# MSP430FR2433_SMD_0603.net
KiCad netlist of a schematic drawn in EAGLE
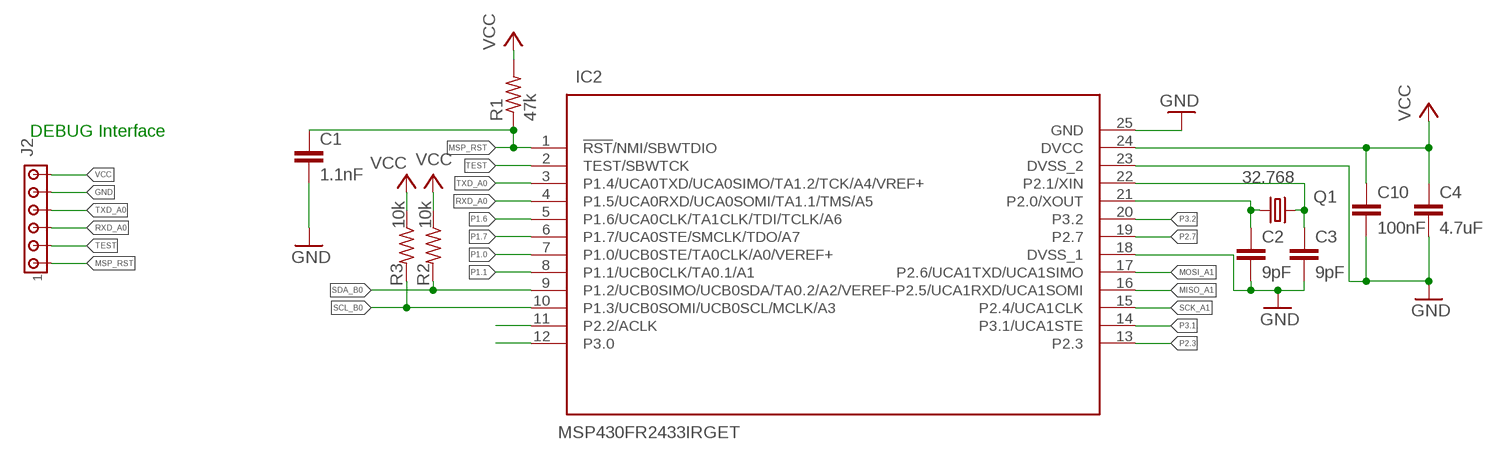
[diagram p0: schematic, sheet 1]

(export (version "E")
  (design (tool "Eeschema 10.0.6"))
  (components
    (comp (ref "C1")
      (value "1.1nF")
      (footprint "eagle-import:C0402")
      (libsource (lib "eagle-import") (part "C-EUC0402"))
    )
    (comp (ref "C2")
      (value "9pF")
      (footprint "eagle-import:C0402")
      (libsource (lib "eagle-import") (part "C-EUC0402"))
    )
    (comp (ref "C3")
      (value "9pF")
      (footprint "eagle-import:C0402")
      (libsource (lib "eagle-import") (part "C-EUC0402"))
    )
    (comp (ref "C4")
      (value "4.7uF")
      (footprint "eagle-import:C0402")
      (libsource (lib "eagle-import") (part "C-EUC0402"))
    )
    (comp (ref "C10")
      (value "100nF")
      (footprint "eagle-import:C0402")
      (libsource (lib "eagle-import") (part "C-EUC0402"))
    )
    (comp (ref "IC2")
      (value "MSP430FR2433IRGET")
      (footprint "eagle-import:QFN50P400X400X100-25N")
      (fields (field (name "MOUSER_PART_NUMBER") "595-SP430FR2433IRGET"))
      (libsource (lib "eagle-import") (part "MSP430FR2433IRGET"))
    )
    (comp (ref "J2")
      (value "MTA06-100")
      (footprint "eagle-import:10X06MTA")
      (libsource (lib "eagle-import") (part "MTA06-100"))
    )
    (comp (ref "Q1")
      (value "32.768")
      (footprint "eagle-import:TC26H")
      (libsource (lib "eagle-import") (part "CRYTALTC26H"))
    )
    (comp (ref "R1")
      (value "47k")
      (footprint "eagle-import:R0402")
      (libsource (lib "eagle-import") (part "R-US_R0402"))
    )
    (comp (ref "R2")
      (value "10k")
      (footprint "eagle-import:R0402")
      (libsource (lib "eagle-import") (part "R-US_R0402"))
    )
    (comp (ref "R3")
      (value "10k")
      (footprint "eagle-import:R0402")
      (libsource (lib "eagle-import") (part "R-US_R0402"))
    )
  )
  (nets
    (net (code "1") (name "GND") (class "Default")
      (node (ref "C1") (pin "2") (pinfunction "2_2") (pintype "passive"))
      (node (ref "C10") (pin "2") (pinfunction "2_2") (pintype "passive"))
      (node (ref "C2") (pin "2") (pinfunction "2_2") (pintype "passive"))
      (node (ref "C3") (pin "2") (pinfunction "2_2") (pintype "passive"))
      (node (ref "C4") (pin "2") (pinfunction "2_2") (pintype "passive"))
      (node (ref "IC2") (pin "18") (pinfunction "DVSS_1_18") (pintype "bidirectional"))
      (node (ref "IC2") (pin "23") (pinfunction "DVSS_2_23") (pintype "bidirectional"))
      (node (ref "IC2") (pin "25") (pinfunction "GND_25") (pintype "bidirectional"))
      (node (ref "J2") (pin "5") (pinfunction "5_5") (pintype "passive"))
    )
    (net (code "2") (name "MISO_A1") (class "Default")
      (node (ref "IC2") (pin "16") (pinfunction "P2.5/UCA1RXD/UCA1SOMI_16") (pintype "bidirectional"))
    )
    (net (code "3") (name "MOSI_A1") (class "Default")
      (node (ref "IC2") (pin "17") (pinfunction "P2.6/UCA1TXD/UCA1SIMO_17") (pintype "bidirectional"))
    )
    (net (code "4") (name "MSP_RST") (class "Default")
      (node (ref "C1") (pin "1") (pinfunction "1_1") (pintype "passive"))
      (node (ref "IC2") (pin "1") (pinfunction "~{RST}/NMI/SBWTDIO_1") (pintype "bidirectional"))
      (node (ref "J2") (pin "1") (pinfunction "1_1") (pintype "passive"))
      (node (ref "R1") (pin "1") (pinfunction "1_1") (pintype "passive"))
    )
    (net (code "5") (name "Net-(IC2-P2.0{slash}XOUT)") (class "Default")
      (node (ref "C2") (pin "1") (pinfunction "1_1") (pintype "passive"))
      (node (ref "IC2") (pin "21") (pinfunction "P2.0/XOUT_21") (pintype "bidirectional"))
      (node (ref "Q1") (pin "1") (pinfunction "1_1") (pintype "passive"))
    )
    (net (code "6") (name "Net-(IC2-P2.1{slash}XIN)") (class "Default")
      (node (ref "C3") (pin "1") (pinfunction "1_1") (pintype "passive"))
      (node (ref "IC2") (pin "22") (pinfunction "P2.1/XIN_22") (pintype "bidirectional"))
      (node (ref "Q1") (pin "2") (pinfunction "2_2") (pintype "passive"))
    )
    (net (code "7") (name "P1.0") (class "Default")
      (node (ref "IC2") (pin "7") (pinfunction "P1.0/UCB0STE/TA0CLK/A0/VEREF+_7") (pintype "bidirectional"))
    )
    (net (code "8") (name "P1.1") (class "Default")
      (node (ref "IC2") (pin "8") (pinfunction "P1.1/UCB0CLK/TA0.1/A1_8") (pintype "bidirectional"))
    )
    (net (code "9") (name "P1.6") (class "Default")
      (node (ref "IC2") (pin "5") (pinfunction "P1.6/UCA0CLK/TA1CLK/TDI/TCLK/A6_5") (pintype "bidirectional"))
    )
    (net (code "10") (name "P1.7") (class "Default")
      (node (ref "IC2") (pin "6") (pinfunction "P1.7/UCA0STE/SMCLK/TDO/A7_6") (pintype "bidirectional"))
    )
    (net (code "11") (name "P2.3") (class "Default")
      (node (ref "IC2") (pin "13") (pinfunction "P2.3_13") (pintype "bidirectional"))
    )
    (net (code "12") (name "P2.7") (class "Default")
      (node (ref "IC2") (pin "19") (pinfunction "P2.7_19") (pintype "bidirectional"))
    )
    (net (code "13") (name "P3.1") (class "Default")
      (node (ref "IC2") (pin "14") (pinfunction "P3.1/UCA1STE_14") (pintype "bidirectional"))
    )
    (net (code "14") (name "P3.2") (class "Default")
      (node (ref "IC2") (pin "20") (pinfunction "P3.2_20") (pintype "bidirectional"))
    )
    (net (code "15") (name "RXD_A0") (class "Default")
      (node (ref "IC2") (pin "4") (pinfunction "P1.5/UCA0RXD/UCA0SOMI/TA1.1/TMS/A5_4") (pintype "bidirectional"))
      (node (ref "J2") (pin "3") (pinfunction "3_3") (pintype "passive"))
    )
    (net (code "16") (name "SCK_A1") (class "Default")
      (node (ref "IC2") (pin "15") (pinfunction "P2.4/UCA1CLK_15") (pintype "bidirectional"))
    )
    (net (code "17") (name "SCL_B0") (class "Default")
      (node (ref "IC2") (pin "10") (pinfunction "P1.3/UCB0SOMI/UCB0SCL/MCLK/A3_10") (pintype "bidirectional"))
      (node (ref "R3") (pin "2") (pinfunction "2_2") (pintype "passive"))
    )
    (net (code "18") (name "SDA_B0") (class "Default")
      (node (ref "IC2") (pin "9") (pinfunction "P1.2/UCB0SIMO/UCB0SDA/TA0.2/A2/VEREF-_9") (pintype "bidirectional"))
      (node (ref "R2") (pin "2") (pinfunction "2_2") (pintype "passive"))
    )
    (net (code "19") (name "TEST") (class "Default")
      (node (ref "IC2") (pin "2") (pinfunction "TEST/SBWTCK_2") (pintype "bidirectional"))
      (node (ref "J2") (pin "2") (pinfunction "2_2") (pintype "passive"))
    )
    (net (code "20") (name "TXD_A0") (class "Default")
      (node (ref "IC2") (pin "3") (pinfunction "P1.4/UCA0TXD/UCA0SIMO/TA1.2/TCK/A4/VREF+_3") (pintype "bidirectional"))
      (node (ref "J2") (pin "4") (pinfunction "4_4") (pintype "passive"))
    )
    (net (code "21") (name "VCC") (class "Default")
      (node (ref "C10") (pin "1") (pinfunction "1_1") (pintype "passive"))
      (node (ref "C4") (pin "1") (pinfunction "1_1") (pintype "passive"))
      (node (ref "IC2") (pin "24") (pinfunction "DVCC_24") (pintype "bidirectional"))
      (node (ref "J2") (pin "6") (pinfunction "6_6") (pintype "passive"))
      (node (ref "R1") (pin "2") (pinfunction "2_2") (pintype "passive"))
      (node (ref "R2") (pin "1") (pinfunction "1_1") (pintype "passive"))
      (node (ref "R3") (pin "1") (pinfunction "1_1") (pintype "passive"))
    )
    (net (code "22") (name "unconnected-(IC2-P2.2{slash}ACLK-Pad11)") (class "Default")
      (node (ref "IC2") (pin "11") (pinfunction "P2.2/ACLK_11") (pintype "bidirectional"))
    )
    (net (code "23") (name "unconnected-(IC2-P3.0-Pad12)") (class "Default")
      (node (ref "IC2") (pin "12") (pinfunction "P3.0_12") (pintype "bidirectional"))
    )
  )
)
